# breakout.net
KiCad netlist of a schematic drawn in EAGLE
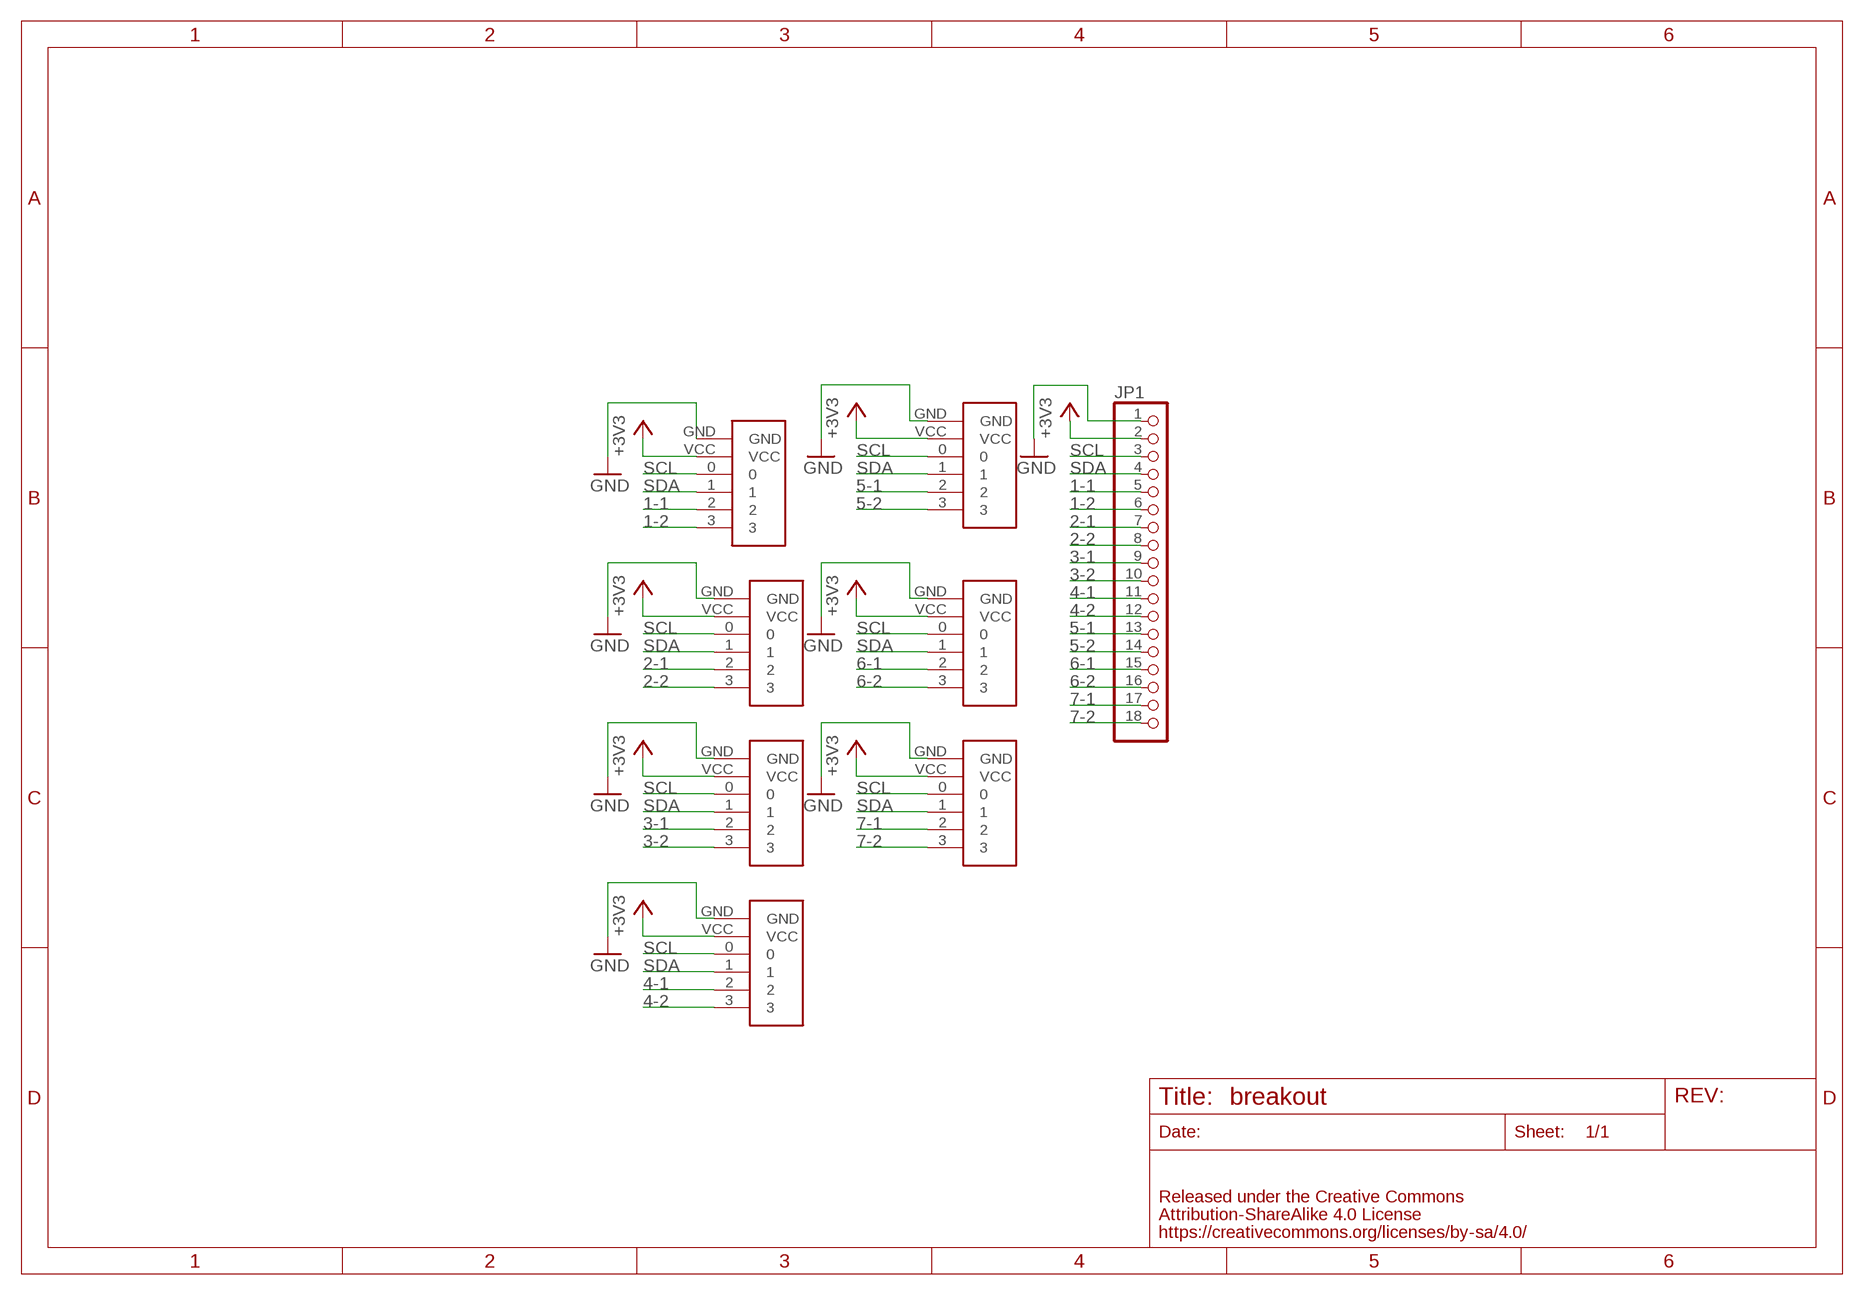
[diagram p0: schematic, sheet 1]

(export (version "E")
  (design (tool "Eeschema 10.0.6"))
  (components
    (comp (ref "1")
      (value "FABO-PIN-HEADER-2X3-SMD")
      (footprint "eagle-import:FABO-PIN-HEADER-2X3-SMD")
      (libsource (lib "eagle-import") (part "FABO-PIN-HEADER-2X3-SMD"))
    )
    (comp (ref "2")
      (value "FABO-PIN-HEADER-2X3-SMD")
      (footprint "eagle-import:FABO-PIN-HEADER-2X3-SMD")
      (libsource (lib "eagle-import") (part "FABO-PIN-HEADER-2X3-SMD"))
    )
    (comp (ref "3")
      (value "FABO-PIN-HEADER-2X3-SMD")
      (footprint "eagle-import:FABO-PIN-HEADER-2X3-SMD")
      (libsource (lib "eagle-import") (part "FABO-PIN-HEADER-2X3-SMD"))
    )
    (comp (ref "4")
      (value "FABO-PIN-HEADER-2X3-SMD")
      (footprint "eagle-import:FABO-PIN-HEADER-2X3-SMD")
      (libsource (lib "eagle-import") (part "FABO-PIN-HEADER-2X3-SMD"))
    )
    (comp (ref "5")
      (value "FABO-PIN-HEADER-2X3-SMD")
      (footprint "eagle-import:FABO-PIN-HEADER-2X3-SMD")
      (libsource (lib "eagle-import") (part "FABO-PIN-HEADER-2X3-SMD"))
    )
    (comp (ref "6")
      (value "FABO-PIN-HEADER-2X3-SMD")
      (footprint "eagle-import:FABO-PIN-HEADER-2X3-SMD")
      (libsource (lib "eagle-import") (part "FABO-PIN-HEADER-2X3-SMD"))
    )
    (comp (ref "7")
      (value "FABO-PIN-HEADER-2X3-SMD")
      (footprint "eagle-import:FABO-PIN-HEADER-2X3-SMD")
      (libsource (lib "eagle-import") (part "FABO-PIN-HEADER-2X3-SMD"))
    )
    (comp (ref "JP1")
      (value "PINHD-1X18")
      (footprint "eagle-import:1X18")
      (libsource (lib "eagle-import") (part "PINHD-1X18"))
    )
  )
  (nets
    (net (code "1") (name "+3V3") (class "Default")
      (node (ref "1") (pin "VCC") (pinfunction "VCC_VCC") (pintype "bidirectional"))
      (node (ref "2") (pin "VCC") (pinfunction "VCC_VCC") (pintype "bidirectional"))
      (node (ref "3") (pin "VCC") (pinfunction "VCC_VCC") (pintype "bidirectional"))
      (node (ref "4") (pin "VCC") (pinfunction "VCC_VCC") (pintype "bidirectional"))
      (node (ref "5") (pin "VCC") (pinfunction "VCC_VCC") (pintype "bidirectional"))
      (node (ref "6") (pin "VCC") (pinfunction "VCC_VCC") (pintype "bidirectional"))
      (node (ref "7") (pin "VCC") (pinfunction "VCC_VCC") (pintype "bidirectional"))
      (node (ref "JP1") (pin "2") (pinfunction "2_2") (pintype "passive"))
    )
    (net (code "2") (name "/1-1") (class "Default")
      (node (ref "1") (pin "2") (pinfunction "2_2") (pintype "bidirectional"))
      (node (ref "JP1") (pin "5") (pinfunction "5_5") (pintype "passive"))
    )
    (net (code "3") (name "/1-2") (class "Default")
      (node (ref "1") (pin "3") (pinfunction "3_3") (pintype "bidirectional"))
      (node (ref "JP1") (pin "6") (pinfunction "6_6") (pintype "passive"))
    )
    (net (code "4") (name "/2-1") (class "Default")
      (node (ref "2") (pin "2") (pinfunction "2_2") (pintype "bidirectional"))
      (node (ref "JP1") (pin "7") (pinfunction "7_7") (pintype "passive"))
    )
    (net (code "5") (name "/2-2") (class "Default")
      (node (ref "2") (pin "3") (pinfunction "3_3") (pintype "bidirectional"))
      (node (ref "JP1") (pin "8") (pinfunction "8_8") (pintype "passive"))
    )
    (net (code "6") (name "/3-1") (class "Default")
      (node (ref "3") (pin "2") (pinfunction "2_2") (pintype "bidirectional"))
      (node (ref "JP1") (pin "9") (pinfunction "9_9") (pintype "passive"))
    )
    (net (code "7") (name "/3-2") (class "Default")
      (node (ref "3") (pin "3") (pinfunction "3_3") (pintype "bidirectional"))
      (node (ref "JP1") (pin "10") (pinfunction "10_10") (pintype "passive"))
    )
    (net (code "8") (name "/4-1") (class "Default")
      (node (ref "4") (pin "2") (pinfunction "2_2") (pintype "bidirectional"))
      (node (ref "JP1") (pin "11") (pinfunction "11_11") (pintype "passive"))
    )
    (net (code "9") (name "/4-2") (class "Default")
      (node (ref "4") (pin "3") (pinfunction "3_3") (pintype "bidirectional"))
      (node (ref "JP1") (pin "12") (pinfunction "12_12") (pintype "passive"))
    )
    (net (code "10") (name "/5-1") (class "Default")
      (node (ref "5") (pin "2") (pinfunction "2_2") (pintype "bidirectional"))
      (node (ref "JP1") (pin "13") (pinfunction "13_13") (pintype "passive"))
    )
    (net (code "11") (name "/5-2") (class "Default")
      (node (ref "5") (pin "3") (pinfunction "3_3") (pintype "bidirectional"))
      (node (ref "JP1") (pin "14") (pinfunction "14_14") (pintype "passive"))
    )
    (net (code "12") (name "/6-1") (class "Default")
      (node (ref "6") (pin "2") (pinfunction "2_2") (pintype "bidirectional"))
      (node (ref "JP1") (pin "15") (pinfunction "15_15") (pintype "passive"))
    )
    (net (code "13") (name "/6-2") (class "Default")
      (node (ref "6") (pin "3") (pinfunction "3_3") (pintype "bidirectional"))
      (node (ref "JP1") (pin "16") (pinfunction "16_16") (pintype "passive"))
    )
    (net (code "14") (name "/7-1") (class "Default")
      (node (ref "7") (pin "2") (pinfunction "2_2") (pintype "bidirectional"))
      (node (ref "JP1") (pin "17") (pinfunction "17_17") (pintype "passive"))
    )
    (net (code "15") (name "/7-2") (class "Default")
      (node (ref "7") (pin "3") (pinfunction "3_3") (pintype "bidirectional"))
      (node (ref "JP1") (pin "18") (pinfunction "18_18") (pintype "passive"))
    )
    (net (code "16") (name "/SCL") (class "Default")
      (node (ref "1") (pin "0") (pinfunction "0_0") (pintype "bidirectional"))
      (node (ref "2") (pin "0") (pinfunction "0_0") (pintype "bidirectional"))
      (node (ref "3") (pin "0") (pinfunction "0_0") (pintype "bidirectional"))
      (node (ref "4") (pin "0") (pinfunction "0_0") (pintype "bidirectional"))
      (node (ref "5") (pin "0") (pinfunction "0_0") (pintype "bidirectional"))
      (node (ref "6") (pin "0") (pinfunction "0_0") (pintype "bidirectional"))
      (node (ref "7") (pin "0") (pinfunction "0_0") (pintype "bidirectional"))
      (node (ref "JP1") (pin "3") (pinfunction "3_3") (pintype "passive"))
    )
    (net (code "17") (name "/SDA") (class "Default")
      (node (ref "1") (pin "1") (pinfunction "1_1") (pintype "bidirectional"))
      (node (ref "2") (pin "1") (pinfunction "1_1") (pintype "bidirectional"))
      (node (ref "3") (pin "1") (pinfunction "1_1") (pintype "bidirectional"))
      (node (ref "4") (pin "1") (pinfunction "1_1") (pintype "bidirectional"))
      (node (ref "5") (pin "1") (pinfunction "1_1") (pintype "bidirectional"))
      (node (ref "6") (pin "1") (pinfunction "1_1") (pintype "bidirectional"))
      (node (ref "7") (pin "1") (pinfunction "1_1") (pintype "bidirectional"))
      (node (ref "JP1") (pin "4") (pinfunction "4_4") (pintype "passive"))
    )
    (net (code "18") (name "GND") (class "Default")
      (node (ref "1") (pin "GND") (pinfunction "GND_GND") (pintype "bidirectional"))
      (node (ref "2") (pin "GND") (pinfunction "GND_GND") (pintype "bidirectional"))
      (node (ref "3") (pin "GND") (pinfunction "GND_GND") (pintype "bidirectional"))
      (node (ref "4") (pin "GND") (pinfunction "GND_GND") (pintype "bidirectional"))
      (node (ref "5") (pin "GND") (pinfunction "GND_GND") (pintype "bidirectional"))
      (node (ref "6") (pin "GND") (pinfunction "GND_GND") (pintype "bidirectional"))
      (node (ref "7") (pin "GND") (pinfunction "GND_GND") (pintype "bidirectional"))
      (node (ref "JP1") (pin "1") (pinfunction "1_1") (pintype "passive"))
    )
  )
)
